# led_driver.net
KiCad netlist of a schematic drawn in EAGLE
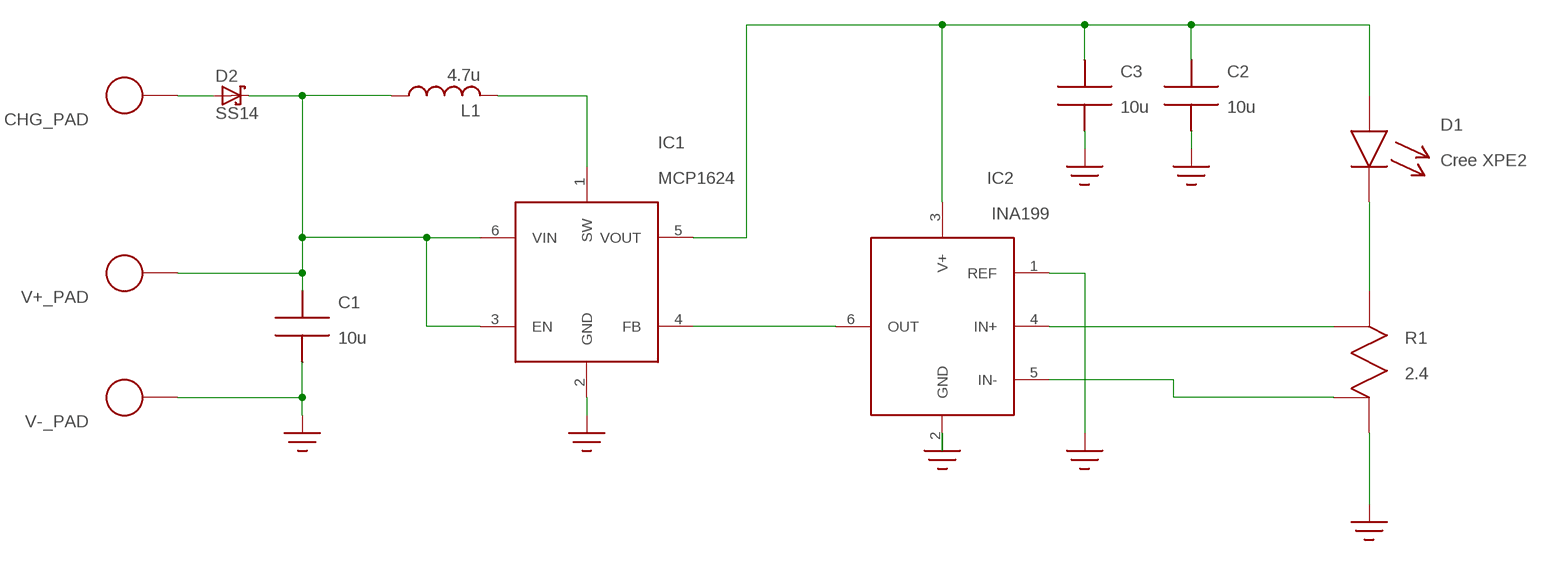
[diagram p0: schematic, sheet 1]

(export (version "E")
  (design (tool "Eeschema 10.0.6"))
  (components
    (comp (ref "C1")
      (value "10u")
      (footprint "eagle-import:1206")
      (libsource (lib "eagle-import") (part "C1206"))
    )
    (comp (ref "C2")
      (value "10u")
      (footprint "eagle-import:1206")
      (libsource (lib "eagle-import") (part "C1206"))
    )
    (comp (ref "C3")
      (value "10u")
      (footprint "eagle-import:1206")
      (libsource (lib "eagle-import") (part "C1206"))
    )
    (comp (ref "CHG_PAD")
      (value "ICSP_PAD100MIL_SQUARE")
      (footprint "eagle-import:100MIL_PAD")
      (libsource (lib "eagle-import") (part "ICSP_PAD100MIL_SQUARE"))
    )
    (comp (ref "D1")
      (value "Cree XPE2")
      (footprint "eagle-import:CREE_XPE_LED")
      (libsource (lib "eagle-import") (part "LEDCREE_XPE"))
    )
    (comp (ref "D2")
      (value "SS14")
      (footprint "eagle-import:SS14")
      (libsource (lib "eagle-import") (part "SS14"))
    )
    (comp (ref "IC1")
      (value "MCP1624")
      (footprint "eagle-import:SOT23-6")
      (libsource (lib "eagle-import") (part "MCP1624"))
    )
    (comp (ref "IC2")
      (value "INA199")
      (footprint "eagle-import:SC70-6")
      (libsource (lib "eagle-import") (part "INA199"))
    )
    (comp (ref "L1")
      (value "4.7u")
      (footprint "eagle-import:4040_INDUCTOR")
      (libsource (lib "eagle-import") (part "INDUCTOR4040"))
    )
    (comp (ref "R1")
      (value "2.4")
      (footprint "eagle-import:R0805_KELVIN")
      (libsource (lib "eagle-import") (part "R_KELVIN"))
    )
    (comp (ref "V+_PAD")
      (value "ICSP_PAD100MIL_SQUARE")
      (footprint "eagle-import:100MIL_PAD")
      (libsource (lib "eagle-import") (part "ICSP_PAD100MIL_SQUARE"))
    )
    (comp (ref "V-_PAD")
      (value "ICSP_PAD100MIL_SQUARE")
      (footprint "eagle-import:100MIL_PAD")
      (libsource (lib "eagle-import") (part "ICSP_PAD100MIL_SQUARE"))
    )
  )
  (nets
    (net (code "1") (name "GND") (class "Default")
      (node (ref "C1") (pin "P$2") (pinfunction "P$2_P$2") (pintype "bidirectional"))
      (node (ref "C2") (pin "P$2") (pinfunction "P$2_P$2") (pintype "bidirectional"))
      (node (ref "C3") (pin "P$2") (pinfunction "P$2_P$2") (pintype "bidirectional"))
      (node (ref "IC1") (pin "2") (pinfunction "GND_2") (pintype "bidirectional"))
      (node (ref "IC2") (pin "1") (pinfunction "REF_1") (pintype "bidirectional"))
      (node (ref "IC2") (pin "2") (pinfunction "GND_2") (pintype "bidirectional"))
      (node (ref "R1") (pin "B1") (pinfunction "B1_B1") (pintype "bidirectional"))
      (node (ref "V-_PAD") (pin "P$1") (pinfunction "P$1_P$1") (pintype "bidirectional"))
    )
    (net (code "2") (name "Net-(CHG_PAD-PadP$1)") (class "Default")
      (node (ref "CHG_PAD") (pin "P$1") (pinfunction "P$1_P$1") (pintype "bidirectional"))
      (node (ref "D2") (pin "A") (pinfunction "A_A") (pintype "passive"))
    )
    (net (code "3") (name "Net-(D1-PadC)") (class "Default")
      (node (ref "D1") (pin "C") (pinfunction "C_C") (pintype "bidirectional"))
      (node (ref "R1") (pin "A1") (pinfunction "A1_A1") (pintype "bidirectional"))
    )
    (net (code "4") (name "Net-(IC1-EN)") (class "Default")
      (node (ref "C1") (pin "P$1") (pinfunction "P$1_P$1") (pintype "bidirectional"))
      (node (ref "D2") (pin "C") (pinfunction "C_C") (pintype "passive"))
      (node (ref "IC1") (pin "3") (pinfunction "EN_3") (pintype "bidirectional"))
      (node (ref "IC1") (pin "6") (pinfunction "VIN_6") (pintype "bidirectional"))
      (node (ref "L1") (pin "P$1") (pinfunction "1_P$1") (pintype "passive"))
      (node (ref "V+_PAD") (pin "P$1") (pinfunction "P$1_P$1") (pintype "bidirectional"))
    )
    (net (code "5") (name "Net-(IC1-FB)") (class "Default")
      (node (ref "IC1") (pin "4") (pinfunction "FB_4") (pintype "bidirectional"))
      (node (ref "IC2") (pin "6") (pinfunction "OUT_6") (pintype "bidirectional"))
    )
    (net (code "6") (name "Net-(IC1-SW)") (class "Default")
      (node (ref "IC1") (pin "1") (pinfunction "SW_1") (pintype "bidirectional"))
      (node (ref "L1") (pin "P$2") (pinfunction "2_P$2") (pintype "passive"))
    )
    (net (code "7") (name "Net-(IC1-VOUT)") (class "Default")
      (node (ref "C2") (pin "P$1") (pinfunction "P$1_P$1") (pintype "bidirectional"))
      (node (ref "C3") (pin "P$1") (pinfunction "P$1_P$1") (pintype "bidirectional"))
      (node (ref "D1") (pin "A") (pinfunction "A_A") (pintype "bidirectional"))
      (node (ref "IC1") (pin "5") (pinfunction "VOUT_5") (pintype "bidirectional"))
      (node (ref "IC2") (pin "3") (pinfunction "V+_3") (pintype "bidirectional"))
    )
    (net (code "8") (name "Net-(IC2-IN+)") (class "Default")
      (node (ref "IC2") (pin "4") (pinfunction "IN+_4") (pintype "bidirectional"))
      (node (ref "R1") (pin "A2") (pinfunction "A2_A2") (pintype "bidirectional"))
    )
    (net (code "9") (name "Net-(IC2-IN-)") (class "Default")
      (node (ref "IC2") (pin "5") (pinfunction "IN-_5") (pintype "bidirectional"))
      (node (ref "R1") (pin "B2") (pinfunction "B2_B2") (pintype "bidirectional"))
    )
  )
)
